# BuckBoost.net
KiCad netlist of a schematic drawn in Altium Designer
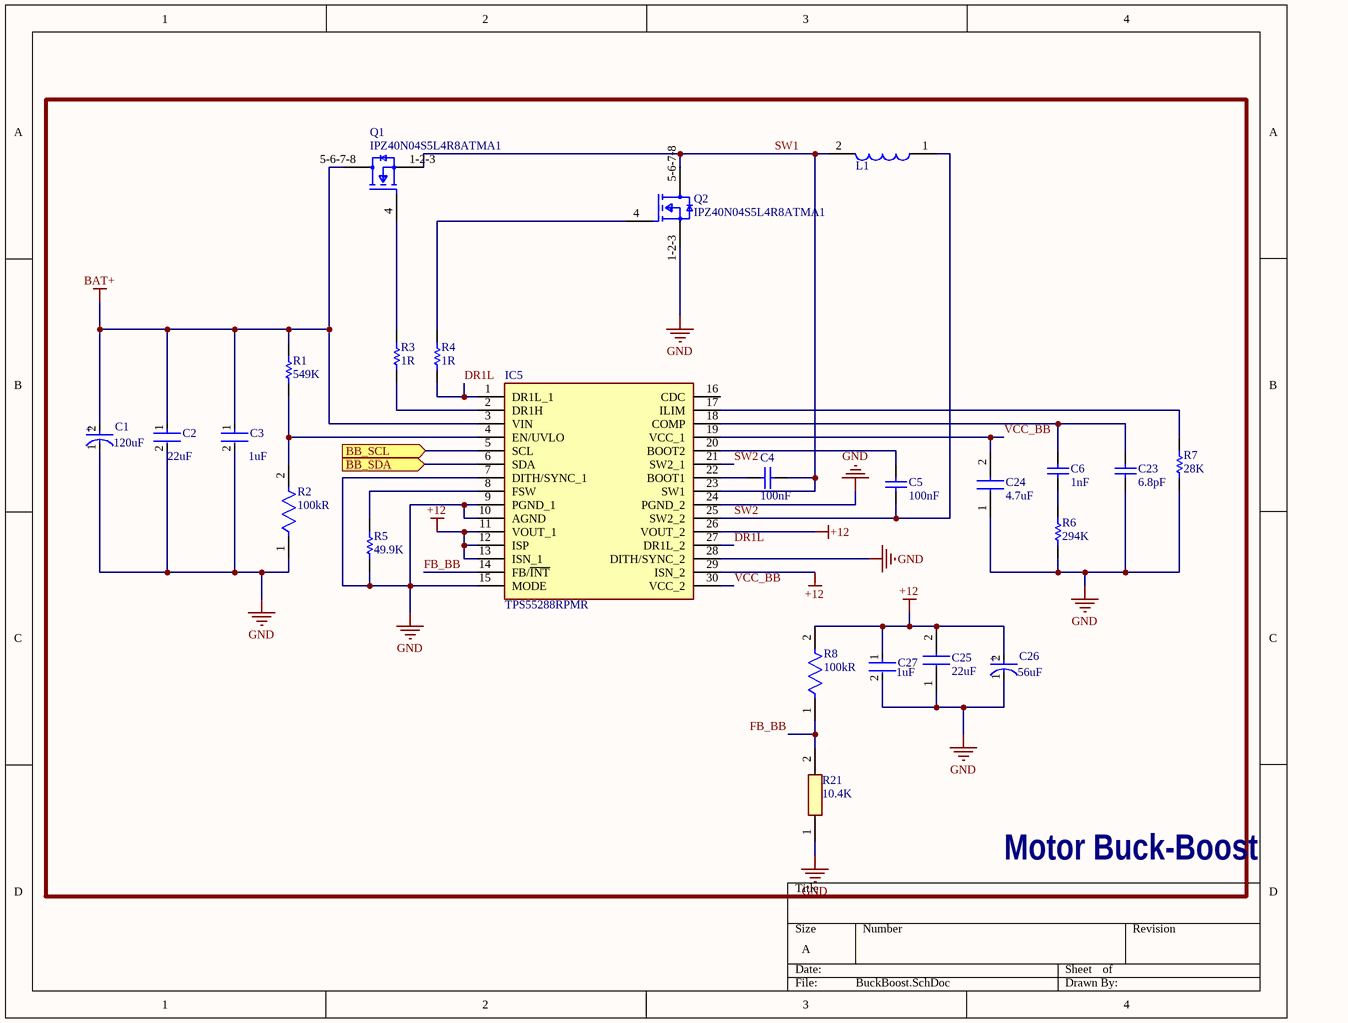
[diagram p0: BuckBoost.SchDoc]

(export (version "E")
  (design (tool "Eeschema 10.0.6"))
  (components
    (comp (ref "C1")
      (value "20SVPF120M")
      (footprint "FP-OS-CON-SMT-C6-MFG")
      (description "Conductive Polymer Aluminum Solid Capacitors (OS-CON) 120uF ±20% 20V")
      (fields
        (field (name "TOLERANCE") "20%")
        (field (name "VOLTAGE") "20V")
        (field (name "CAPACITANCE") "120uF")
      )
      (libsource (lib "Altium Content Vault") (part "a00bbbee19879c290e62620ae7e47b1"))
    )
    (comp (ref "C2")
      (value "GRM32ER61E226KE15L")
      (footprint "FP-GRM32-MFG")
      (description "CAP CER 22UF 25V X5R 1210")
      (fields
        (field (name "CAPACITANCE") "22uF")
        (field (name "TOLERANCE") "10%")
        (field (name "MANUFACTURER") "Murata Electronics North America")
      )
      (libsource (lib "Altium Content Vault") (part "11868f565c42a9108669ba33697ecf6"))
    )
    (comp (ref "C3")
      (value "C1005X5R1V105K050BC")
      (footprint "FP-C1005-050-0_05-IPC_C")
      (description "Multilayer Ceramic Capacitors 1μF ±10% 35V X5R SMD 0402")
      (fields (field (name "CAPACITANCE") "1uF") (field (name "TOLERANCE") "10%"))
      (libsource (lib "Altium Content Vault") (part "b4654b650e69147ec39a6b967a45e02"))
    )
    (comp (ref "C4")
      (value "CL05B104KO5NNNC")
      (footprint "CAPC1050X55X23ML05T13")
      (description "Chip Capacitor, 100 nF, +/- 10%, 16 V, -55 to 125 degC, 0402 (1005 Metric), RoHS, Tape and Reel")
      (fields (field (name "MANUFACTURER") "Samsung Electro-Mechanics") (field (name "CAPACITANCE") "100nF"))
      (libsource (lib "Altium Content Vault") (part "CAP-NP-2"))
    )
    (comp (ref "C5")
      (value "CL05B104KO5NNNC")
      (footprint "CAPC1050X55X23ML05T13")
      (description "Chip Capacitor, 100 nF, +/- 10%, 16 V, -55 to 125 degC, 0402 (1005 Metric), RoHS, Tape and Reel")
      (fields (field (name "MANUFACTURER") "Samsung Electro-Mechanics") (field (name "CAPACITANCE") "100nF"))
      (libsource (lib "Altium Content Vault") (part "CAP-NP-2"))
    )
    (comp (ref "C6")
      (value "GRM155R71C102KA01D")
      (footprint "CAPC1005X55X25NL05T10")
      (fields (field (name "MANUFACTURER") "Murata") (field (name "CAPACITANCE") "1nF"))
      (libsource (lib "Altium Content Vault") (part "CAP"))
    )
    (comp (ref "C23")
      (value "GRM1555C1E6R8CA01D")
      (footprint "CAPC1005X55X25NL05T10")
      (fields (field (name "MANUFACTURER") "Murata") (field (name "CAPACITANCE") "6.8pF"))
      (libsource (lib "Altium Content Vault") (part "CAP"))
    )
    (comp (ref "C24")
      (value "C1608X6S1C475K080AC")
      (footprint "SamacSys:CAPC1608X80N")
      (description "Capacitor")
      (fields (field (name "MOUSER PART NUMBER") "810-C1608X6S1C475K") (field (name "CAPACITANCE") "4.7uF"))
      (libsource (lib "*") (part "C1608X6S1C475K080AC"))
    )
    (comp (ref "C25")
      (value "CGA9P2X7R1E226M250KA")
      (footprint "SamacSys:CAPC5750X280N")
      (description "Capacitor")
      (fields (field (name "MOUSER PART NUMBER") "810-CGA9P2X7R1E226M") (field (name "CAPACITANCE") "22uF"))
      (libsource (lib "*") (part "CGA9P2X7R1E226M250KA"))
    )
    (comp (ref "C26")
      (value "20SVPF56MX")
      (footprint "FP-OS-CON-SMT-B6-MFG")
      (description "Conductive Polymer Aluminum Solid Capacitors (OS-CON) 56uF ±20% 20V")
      (fields
        (field (name "TOLERANCE") "20%")
        (field (name "VOLTAGE") "20V")
        (field (name "CAPACITANCE") "56uF")
      )
      (libsource (lib "Altium Content Vault") (part "a00bbbee19879c290e62620ae7e47b1"))
    )
    (comp (ref "C27")
      (value "C1005X5R1V105K050BC")
      (footprint "FP-C1005-050-0_05-IPC_C")
      (description "Multilayer Ceramic Capacitors 1μF ±10% 35V X5R SMD 0402")
      (fields (field (name "CAPACITANCE") "1uF") (field (name "TOLERANCE") "10%"))
      (libsource (lib "Altium Content Vault") (part "b4654b650e69147ec39a6b967a45e02"))
    )
    (comp (ref "IC5")
      (value "TPS55288RPMR")
      (footprint "SamacSys:TPS55288RPMR")
      (description "Integrated Circuit")
      (fields (field (name "MOUSER PART NUMBER") "595-TPS55288RPMR"))
      (libsource (lib "*") (part "TPS55288RPMR"))
    )
    (comp (ref "L1")
      (value "XAL6030-182MEB")
      (footprint "SamacSys:XAL6030182MEB")
      (description "Inductor")
      (fields (field (name "MOUSER PART NUMBER") "994-XAL6030-182MEB"))
      (libsource (lib "*") (part "XAL6030-182MEB"))
    )
    (comp (ref "Q1")
      (value "IPZ40N04S5L4R8ATMA1")
      (footprint "FP-PG-TSDSON-8-MFG")
      (description "MOSFET N-CH 40V 40A 8TSDSON")
      (libsource (lib "Altium Content Vault") (part "3085234d4498bcd04bc7e5400bb7c96"))
    )
    (comp (ref "Q2")
      (value "IPZ40N04S5L4R8ATMA1")
      (footprint "FP-PG-TSDSON-8-MFG")
      (description "MOSFET N-CH 40V 40A 8TSDSON")
      (libsource (lib "Altium Content Vault") (part "3085234d4498bcd04bc7e5400bb7c96"))
    )
    (comp (ref "R1")
      (value "CRCW0402549KFKED")
      (footprint "RESC1005X40X25LL05T05")
      (fields (field (name "MANUFACTURER") "Vishay Dale") (field (name "RESISTANCE") "549K"))
      (libsource (lib "Altium Content Vault") (part "RES"))
    )
    (comp (ref "R2")
      (value "CRCW0402100KFKED")
      (footprint "FP-CRCW0402-e3-IPC_C")
      (description "RES Thick Film, 100kΩ, 1%, 0.063W, 100ppm/°C, 0402")
      (fields (field (name "RESISTANCE") "100kR") (field (name "TOLERANCE") "1%"))
      (libsource (lib "Altium Content Vault") (part "1029c3af85768c4190bb7ad29bc67b5"))
    )
    (comp (ref "R3")
      (value "CRCW06031R00FKEA")
      (footprint "RESC1609X50X30NL10T20")
      (fields (field (name "MANUFACTURER") "Vishay Dale") (field (name "RESISTANCE") "1R"))
      (libsource (lib "Altium Content Vault") (part "RES"))
    )
    (comp (ref "R4")
      (value "CRCW06031R00FKEA")
      (footprint "RESC1609X50X30NL10T20")
      (fields (field (name "MANUFACTURER") "Vishay Dale") (field (name "RESISTANCE") "1R"))
      (libsource (lib "Altium Content Vault") (part "RES"))
    )
    (comp (ref "R5")
      (value "CRCW040249K9FKED")
      (footprint "RESC1005X40X25LL05T05")
      (fields (field (name "MANUFACTURER") "Vishay Dale") (field (name "RESISTANCE") "49.9K"))
      (libsource (lib "Altium Content Vault") (part "RES"))
    )
    (comp (ref "R6")
      (value "CRCW0402294KFKED")
      (footprint "RESC1005X40X25LL05T05")
      (fields (field (name "MANUFACTURER") "Vishay Dale") (field (name "RESISTANCE") "294K"))
      (libsource (lib "Altium Content Vault") (part "RES"))
    )
    (comp (ref "R7")
      (value "CRCW040228K0FKED")
      (footprint "RESC1005X40X25NL05T05")
      (fields (field (name "MANUFACTURER") "Vishay Dale") (field (name "RESISTANCE") "28K"))
      (libsource (lib "Altium Content Vault") (part "RES"))
    )
    (comp (ref "R8")
      (value "CRCW0402100KFKED")
      (footprint "FP-CRCW0402-e3-IPC_C")
      (description "RES Thick Film, 100kΩ, 1%, 0.063W, 100ppm/°C, 0402")
      (fields (field (name "RESISTANCE") "100kR") (field (name "TOLERANCE") "1%"))
      (libsource (lib "Altium Content Vault") (part "1029c3af85768c4190bb7ad29bc67b5"))
    )
    (comp (ref "R21")
      (value "RT0805BRD0710K4L")
      (footprint "SamacSys:RESC2012X60N")
      (description "Resistor")
      (fields (field (name "MOUSER PART NUMBER") "603-RT0805BRD0710K4L") (field (name "RESISTANCE") "10.4K"))
      (libsource (lib "*") (part "RT0805BRD0710K4L"))
    )
  )
  (nets
    (net (code "1") (name "+12") (class "Default")
      (node (ref "C25") (pin "2") (pinfunction "2_2") (pintype "passive"))
      (node (ref "C26") (pin "2") (pinfunction "A_2") (pintype "passive"))
      (node (ref "C27") (pin "1") (pinfunction "1_1") (pintype "passive"))
      (node (ref "IC5") (pin "11") (pinfunction "VOUT_1_11") (pintype "passive"))
      (node (ref "IC5") (pin "12") (pinfunction "ISP_12") (pintype "passive"))
      (node (ref "IC5") (pin "13") (pinfunction "ISN_1_13") (pintype "passive"))
      (node (ref "IC5") (pin "26") (pinfunction "VOUT_2_26") (pintype "passive"))
      (node (ref "IC5") (pin "29") (pinfunction "ISN_2_29") (pintype "passive"))
      (node (ref "R8") (pin "2") (pinfunction "2_2") (pintype "passive"))
    )
    (net (code "2") (name "/BB_SCL") (class "Default")
      (node (ref "IC5") (pin "5") (pinfunction "SCL_5") (pintype "passive"))
    )
    (net (code "3") (name "/BB_SDA") (class "Default")
      (node (ref "IC5") (pin "6") (pinfunction "SDA_6") (pintype "passive"))
    )
    (net (code "4") (name "/DR1L") (class "Default")
      (node (ref "IC5") (pin "1") (pinfunction "DR1L_1_1") (pintype "passive"))
      (node (ref "IC5") (pin "27") (pinfunction "DR1L_2_27") (pintype "passive"))
      (node (ref "R4") (pin "1") (pinfunction "1_1") (pintype "passive"))
    )
    (net (code "5") (name "/FB_BB") (class "Default")
      (node (ref "IC5") (pin "14") (pinfunction "FB/~{INT}_14") (pintype "passive"))
      (node (ref "R21") (pin "2") (pinfunction "2_2") (pintype "passive"))
      (node (ref "R8") (pin "1") (pinfunction "1_1") (pintype "passive"))
    )
    (net (code "6") (name "/SW1") (class "Default")
      (node (ref "C4") (pin "1") (pinfunction "1_1") (pintype "passive"))
      (node (ref "IC5") (pin "23") (pinfunction "SW1_23") (pintype "passive"))
      (node (ref "L1") (pin "2") (pinfunction "2_2") (pintype "passive"))
      (node (ref "Q1") (pin "1-2-3") (pinfunction "S_1-2-3") (pintype "passive"))
      (node (ref "Q2") (pin "5-6-7-8") (pinfunction "D_5-6-7-8") (pintype "passive"))
    )
    (net (code "7") (name "/SW2") (class "Default")
      (node (ref "C5") (pin "2") (pinfunction "2_2") (pintype "passive"))
      (node (ref "IC5") (pin "21") (pinfunction "SW2_1_21") (pintype "passive"))
      (node (ref "IC5") (pin "25") (pinfunction "SW2_2_25") (pintype "passive"))
      (node (ref "L1") (pin "1") (pinfunction "1_1") (pintype "passive"))
    )
    (net (code "8") (name "/VCC_BB") (class "Default")
      (node (ref "C24") (pin "2") (pinfunction "2_2") (pintype "passive"))
      (node (ref "IC5") (pin "19") (pinfunction "VCC_1_19") (pintype "passive"))
      (node (ref "IC5") (pin "30") (pinfunction "VCC_2_30") (pintype "passive"))
    )
    (net (code "9") (name "BAT+") (class "Default")
      (node (ref "C1") (pin "2") (pinfunction "A_2") (pintype "passive"))
      (node (ref "C2") (pin "1") (pinfunction "1_1") (pintype "passive"))
      (node (ref "C3") (pin "1") (pinfunction "1_1") (pintype "passive"))
      (node (ref "IC5") (pin "3") (pinfunction "VIN_3") (pintype "passive"))
      (node (ref "Q1") (pin "5-6-7-8") (pinfunction "D_5-6-7-8") (pintype "passive"))
      (node (ref "R1") (pin "2") (pinfunction "2_2") (pintype "passive"))
    )
    (net (code "10") (name "GND") (class "Default")
      (node (ref "C1") (pin "1") (pinfunction "C_1") (pintype "passive"))
      (node (ref "C2") (pin "2") (pinfunction "2_2") (pintype "passive"))
      (node (ref "C23") (pin "1") (pinfunction "1_1") (pintype "passive"))
      (node (ref "C24") (pin "1") (pinfunction "1_1") (pintype "passive"))
      (node (ref "C25") (pin "1") (pinfunction "1_1") (pintype "passive"))
      (node (ref "C26") (pin "1") (pinfunction "C_1") (pintype "passive"))
      (node (ref "C27") (pin "2") (pinfunction "2_2") (pintype "passive"))
      (node (ref "C3") (pin "2") (pinfunction "2_2") (pintype "passive"))
      (node (ref "IC5") (pin "10") (pinfunction "AGND_10") (pintype "passive"))
      (node (ref "IC5") (pin "15") (pinfunction "MODE_15") (pintype "passive"))
      (node (ref "IC5") (pin "24") (pinfunction "PGND_2_24") (pintype "passive"))
      (node (ref "IC5") (pin "28") (pinfunction "DITH/SYNC_2_28") (pintype "passive"))
      (node (ref "IC5") (pin "7") (pinfunction "DITH/SYNC_1_7") (pintype "passive"))
      (node (ref "IC5") (pin "9") (pinfunction "PGND_1_9") (pintype "passive"))
      (node (ref "Q2") (pin "1-2-3") (pinfunction "S_1-2-3") (pintype "passive"))
      (node (ref "R2") (pin "1") (pinfunction "1_1") (pintype "passive"))
      (node (ref "R21") (pin "1") (pinfunction "1_1") (pintype "passive"))
      (node (ref "R5") (pin "1") (pinfunction "1_1") (pintype "passive"))
      (node (ref "R6") (pin "1") (pinfunction "1_1") (pintype "passive"))
      (node (ref "R7") (pin "1") (pinfunction "1_1") (pintype "passive"))
    )
    (net (code "11") (name "Net-(C6-Pad1)") (class "Default")
      (node (ref "C6") (pin "1") (pinfunction "1_1") (pintype "passive"))
      (node (ref "R6") (pin "2") (pinfunction "2_2") (pintype "passive"))
    )
    (net (code "12") (name "Net-(IC5-BOOT1)") (class "Default")
      (node (ref "C4") (pin "2") (pinfunction "2_2") (pintype "passive"))
      (node (ref "IC5") (pin "22") (pinfunction "BOOT1_22") (pintype "passive"))
    )
    (net (code "13") (name "Net-(IC5-BOOT2)") (class "Default")
      (node (ref "C5") (pin "1") (pinfunction "1_1") (pintype "passive"))
      (node (ref "IC5") (pin "20") (pinfunction "BOOT2_20") (pintype "passive"))
    )
    (net (code "14") (name "Net-(IC5-COMP)") (class "Default")
      (node (ref "C23") (pin "2") (pinfunction "2_2") (pintype "passive"))
      (node (ref "C6") (pin "2") (pinfunction "2_2") (pintype "passive"))
      (node (ref "IC5") (pin "18") (pinfunction "COMP_18") (pintype "passive"))
    )
    (net (code "15") (name "Net-(IC5-DR1H)") (class "Default")
      (node (ref "IC5") (pin "2") (pinfunction "DR1H_2") (pintype "passive"))
      (node (ref "R3") (pin "1") (pinfunction "1_1") (pintype "passive"))
    )
    (net (code "16") (name "Net-(IC5-EN{slash}UVLO)") (class "Default")
      (node (ref "IC5") (pin "4") (pinfunction "EN/UVLO_4") (pintype "passive"))
      (node (ref "R1") (pin "1") (pinfunction "1_1") (pintype "passive"))
      (node (ref "R2") (pin "2") (pinfunction "2_2") (pintype "passive"))
    )
    (net (code "17") (name "Net-(IC5-FSW)") (class "Default")
      (node (ref "IC5") (pin "8") (pinfunction "FSW_8") (pintype "passive"))
      (node (ref "R5") (pin "2") (pinfunction "2_2") (pintype "passive"))
    )
    (net (code "18") (name "Net-(IC5-ILIM)") (class "Default")
      (node (ref "IC5") (pin "17") (pinfunction "ILIM_17") (pintype "passive"))
      (node (ref "R7") (pin "2") (pinfunction "2_2") (pintype "passive"))
    )
    (net (code "19") (name "Net-(Q1-G)") (class "Default")
      (node (ref "Q1") (pin "4") (pinfunction "G_4") (pintype "passive"))
      (node (ref "R3") (pin "2") (pinfunction "2_2") (pintype "passive"))
    )
    (net (code "20") (name "Net-(Q2-G)") (class "Default")
      (node (ref "Q2") (pin "4") (pinfunction "G_4") (pintype "passive"))
      (node (ref "R4") (pin "2") (pinfunction "2_2") (pintype "passive"))
    )
    (net (code "21") (name "unconnected-(IC5-CDC-Pad16)") (class "Default")
      (node (ref "IC5") (pin "16") (pinfunction "CDC_16") (pintype "passive"))
    )
  )
)
